# BiasController.net
KiCad netlist of a schematic drawn in EAGLE
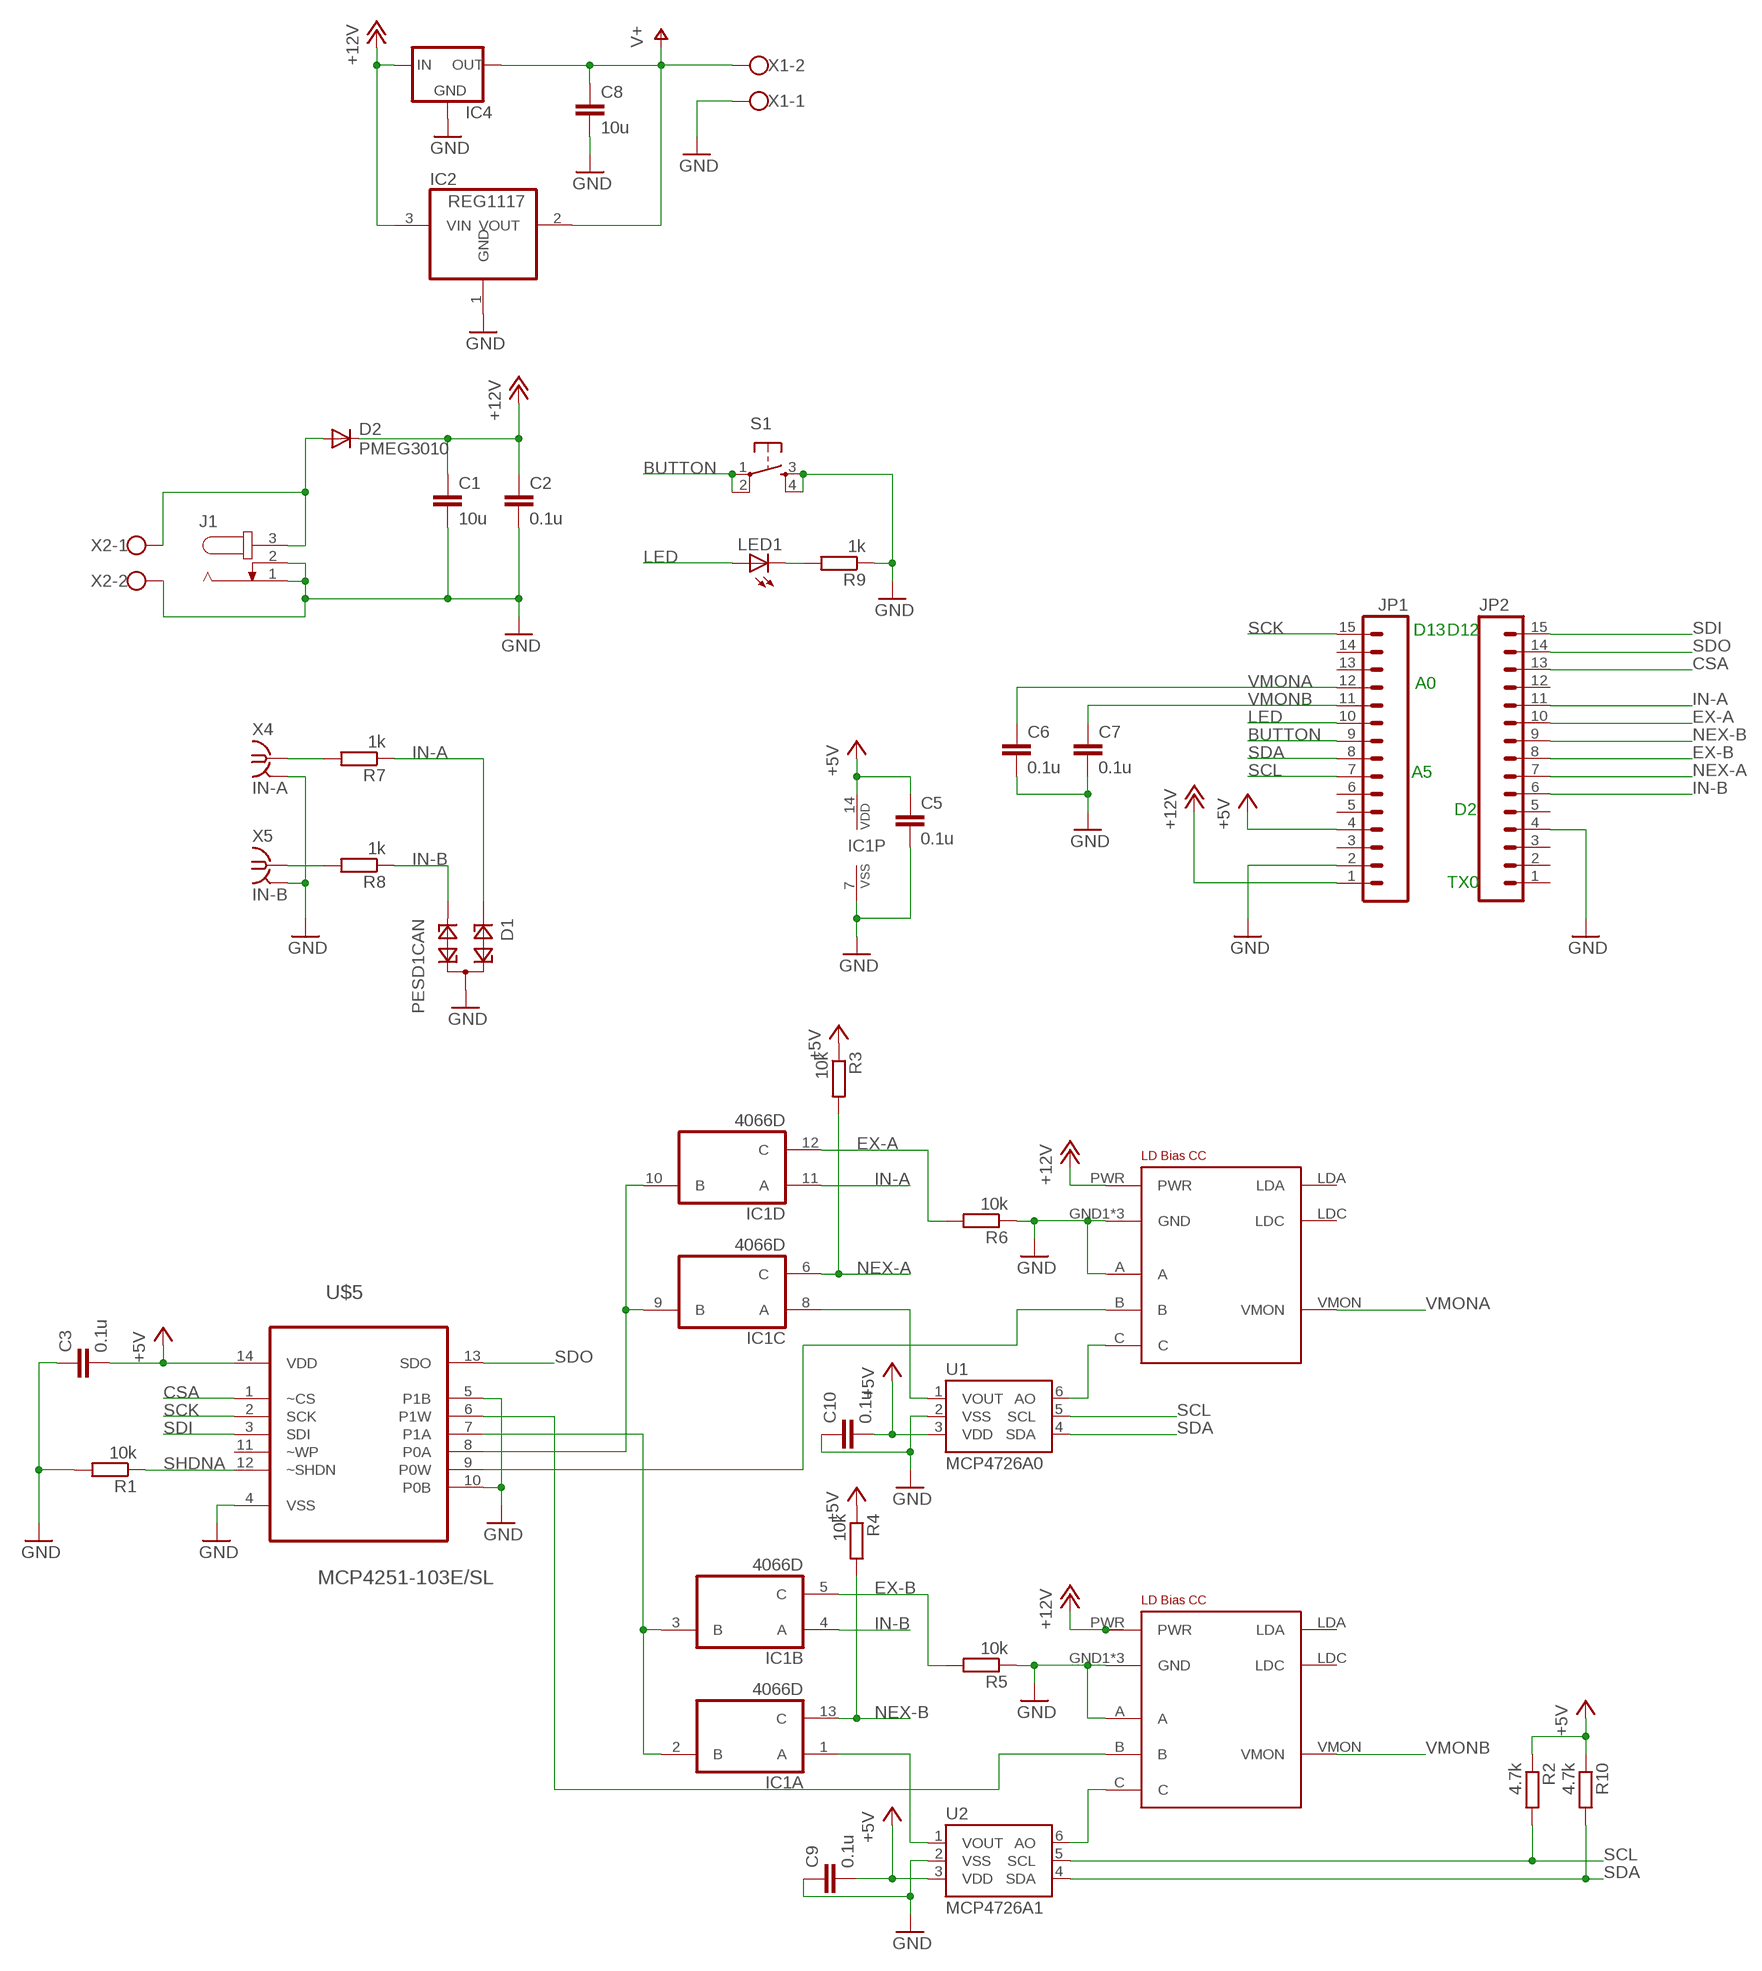
[diagram p0: schematic, sheet 1]

(export (version "E")
  (design (tool "Eeschema 10.0.6"))
  (components
    (comp (ref "C1")
      (value "10u")
      (footprint "eagle-import:C0805")
      (libsource (lib "eagle-import") (part "C-EUC0805"))
    )
    (comp (ref "C2")
      (value "0.1u")
      (footprint "eagle-import:C0805")
      (libsource (lib "eagle-import") (part "C-EUC0805"))
    )
    (comp (ref "C3")
      (value "0.1u")
      (footprint "eagle-import:C0805")
      (libsource (lib "eagle-import") (part "C-EUC0805"))
    )
    (comp (ref "C5")
      (value "0.1u")
      (footprint "eagle-import:C0805")
      (libsource (lib "eagle-import") (part "C-EUC0805"))
    )
    (comp (ref "C6")
      (value "0.1u")
      (footprint "eagle-import:C0805")
      (libsource (lib "eagle-import") (part "C-EUC0805"))
    )
    (comp (ref "C7")
      (value "0.1u")
      (footprint "eagle-import:C0805")
      (libsource (lib "eagle-import") (part "C-EUC0805"))
    )
    (comp (ref "C8")
      (value "10u")
      (footprint "eagle-import:C0805")
      (libsource (lib "eagle-import") (part "C-EUC0805"))
    )
    (comp (ref "C9")
      (value "0.1u")
      (footprint "eagle-import:C0805")
      (libsource (lib "eagle-import") (part "C-EUC0805"))
    )
    (comp (ref "C10")
      (value "0.1u")
      (footprint "eagle-import:C0805")
      (libsource (lib "eagle-import") (part "C-EUC0805"))
    )
    (comp (ref "D1")
      (value "PESD1CAN")
      (footprint "eagle-import:SOT23")
      (libsource (lib "eagle-import") (part "PESD1CAN"))
    )
    (comp (ref "D2")
      (value "PMEG3010")
      (footprint "eagle-import:SOD-323")
      (libsource (lib "eagle-import") (part "DIODESOD"))
    )
    (comp (ref "IC1")
      (value "4066D")
      (footprint "eagle-import:SO14")
      (libsource (lib "eagle-import") (part "4066D"))
    )
    (comp (ref "IC2")
      (value "REG1117")
      (footprint "eagle-import:SOT223")
      (libsource (lib "eagle-import") (part "REG1117"))
    )
    (comp (ref "IC4")
      (value "78XXS")
      (footprint "eagle-import:78XXS")
      (libsource (lib "eagle-import") (part "78XXS"))
    )
    (comp (ref "J1")
      (value "JACK-PLUG0")
      (footprint "eagle-import:SPC4077")
      (libsource (lib "eagle-import") (part "JACK-PLUG0"))
    )
    (comp (ref "JP1")
      (value "M15LOCK_LONGPADS")
      (footprint "eagle-import:1X15_LOCK_LONGPADS")
      (libsource (lib "eagle-import") (part "M15LOCK_LONGPADS"))
    )
    (comp (ref "JP2")
      (value "M15LOCK_LONGPADS")
      (footprint "eagle-import:1X15_LOCK_LONGPADS")
      (libsource (lib "eagle-import") (part "M15LOCK_LONGPADS"))
    )
    (comp (ref "LED1")
      (value "LED0603")
      (footprint "eagle-import:LED-0603")
      (libsource (lib "eagle-import") (part "LED0603"))
    )
    (comp (ref "R1")
      (value "10k")
      (footprint "eagle-import:R0805")
      (libsource (lib "eagle-import") (part "R-EU_R0805"))
    )
    (comp (ref "R2")
      (value "4.7k")
      (footprint "eagle-import:R0805")
      (libsource (lib "eagle-import") (part "R-EU_R0805"))
    )
    (comp (ref "R3")
      (value "10k")
      (footprint "eagle-import:R0805")
      (libsource (lib "eagle-import") (part "R-EU_R0805"))
    )
    (comp (ref "R4")
      (value "10k")
      (footprint "eagle-import:R0805")
      (libsource (lib "eagle-import") (part "R-EU_R0805"))
    )
    (comp (ref "R5")
      (value "10k")
      (footprint "eagle-import:R0805")
      (libsource (lib "eagle-import") (part "R-EU_R0805"))
    )
    (comp (ref "R6")
      (value "10k")
      (footprint "eagle-import:R0805")
      (libsource (lib "eagle-import") (part "R-EU_R0805"))
    )
    (comp (ref "R7")
      (value "1k")
      (footprint "eagle-import:R0805")
      (libsource (lib "eagle-import") (part "R-EU_R0805"))
    )
    (comp (ref "R8")
      (value "1k")
      (footprint "eagle-import:R0805")
      (libsource (lib "eagle-import") (part "R-EU_R0805"))
    )
    (comp (ref "R9")
      (value "1k")
      (footprint "eagle-import:R0805")
      (libsource (lib "eagle-import") (part "R-EU_R0805"))
    )
    (comp (ref "R10")
      (value "4.7k")
      (footprint "eagle-import:R0805")
      (libsource (lib "eagle-import") (part "R-EU_R0805"))
    )
    (comp (ref "S1")
      (value "TAC_SWITCHPTH")
      (footprint "eagle-import:TACTILE-PTH")
      (libsource (lib "eagle-import") (part "TAC_SWITCHPTH"))
    )
    (comp (ref "U$1")
      (value "LDBIASCC")
      (footprint "eagle-import:LDBIASDRIVERCC")
      (libsource (lib "eagle-import") (part "LDBIASCC"))
    )
    (comp (ref "U$2")
      (value "LDBIASCC")
      (footprint "eagle-import:LDBIASDRIVERCC")
      (libsource (lib "eagle-import") (part "LDBIASCC"))
    )
    (comp (ref "U$5")
      (value "MCP4251-103E/SL")
      (footprint "eagle-import:SOIC127P600X175-14N")
      (libsource (lib "eagle-import") (part "MCP4251-103E/SL"))
    )
    (comp (ref "U1")
      (value "MCP4726A0")
      (footprint "eagle-import:SOT23-6")
      (libsource (lib "eagle-import") (part "MCP4725SOT-23"))
    )
    (comp (ref "U2")
      (value "MCP4726A1")
      (footprint "eagle-import:SOT23-6")
      (libsource (lib "eagle-import") (part "MCP4725SOT-23"))
    )
    (comp (ref "X1")
      (value "W237-102")
      (footprint "eagle-import:W237-102")
      (fields (field (name "MPN") "237-102"))
      (libsource (lib "eagle-import") (part "W237-102"))
    )
    (comp (ref "X2")
      (value "W237-102")
      (footprint "eagle-import:W237-102")
      (fields (field (name "MPN") "237-102"))
      (libsource (lib "eagle-import") (part "W237-102"))
    )
    (comp (ref "X4")
      (value "IN-A")
      (footprint "eagle-import:J502-ND-142-0711-821_826")
      (fields (field (name "MF") "JOHNSON COMPONENTS") (field (name "MPN") "142-0711-821"))
      (libsource (lib "eagle-import") (part "SMA-142-0711-821/826"))
    )
    (comp (ref "X5")
      (value "IN-B")
      (footprint "eagle-import:J502-ND-142-0711-821_826")
      (fields (field (name "MF") "JOHNSON COMPONENTS") (field (name "MPN") "142-0711-821"))
      (libsource (lib "eagle-import") (part "SMA-142-0711-821/826"))
    )
  )
  (nets
    (net (code "1") (name "+5V") (class "Default")
      (node (ref "C10") (pin "2") (pinfunction "2_2") (pintype "passive"))
      (node (ref "C3") (pin "2") (pinfunction "2_2") (pintype "passive"))
      (node (ref "C5") (pin "1") (pinfunction "1_1") (pintype "passive"))
      (node (ref "C9") (pin "2") (pinfunction "2_2") (pintype "passive"))
      (node (ref "IC1") (pin "14") (pinfunction "VDD_14") (pintype "power_in"))
      (node (ref "JP1") (pin "4") (pinfunction "4_4") (pintype "passive"))
      (node (ref "R10") (pin "1") (pinfunction "1_1") (pintype "passive"))
      (node (ref "R2") (pin "1") (pinfunction "1_1") (pintype "passive"))
      (node (ref "R3") (pin "1") (pinfunction "1_1") (pintype "passive"))
      (node (ref "R4") (pin "1") (pinfunction "1_1") (pintype "passive"))
      (node (ref "U$5") (pin "14") (pinfunction "VDD_14") (pintype "power_in"))
      (node (ref "U1") (pin "3") (pinfunction "VDD_3") (pintype "bidirectional"))
      (node (ref "U2") (pin "3") (pinfunction "VDD_3") (pintype "bidirectional"))
    )
    (net (code "2") (name "+12V") (class "Default")
      (node (ref "C1") (pin "1") (pinfunction "1_1") (pintype "passive"))
      (node (ref "C2") (pin "1") (pinfunction "1_1") (pintype "passive"))
      (node (ref "D2") (pin "1") (pinfunction "C_1") (pintype "passive"))
      (node (ref "IC2") (pin "3") (pinfunction "VIN_3") (pintype "input"))
      (node (ref "IC4") (pin "IN") (pinfunction "IN_IN") (pintype "input"))
      (node (ref "JP1") (pin "1") (pinfunction "1_1") (pintype "passive"))
      (node (ref "U$1") (pin "PWR") (pinfunction "PWR_PWR") (pintype "bidirectional"))
      (node (ref "U$2") (pin "PWR") (pinfunction "PWR_PWR") (pintype "bidirectional"))
    )
    (net (code "3") (name "/BUTTON") (class "Default")
      (node (ref "JP1") (pin "9") (pinfunction "9_9") (pintype "passive"))
      (node (ref "S1") (pin "1") (pinfunction "1_1") (pintype "passive"))
      (node (ref "S1") (pin "2") (pinfunction "2_2") (pintype "passive"))
    )
    (net (code "4") (name "/CSA") (class "Default")
      (node (ref "JP2") (pin "13") (pinfunction "13_13") (pintype "passive"))
      (node (ref "U$5") (pin "1") (pinfunction "~{CS}_1") (pintype "input"))
    )
    (net (code "5") (name "/EX-A") (class "Default")
      (node (ref "IC1") (pin "12") (pinfunction "C_12") (pintype "input"))
      (node (ref "JP2") (pin "10") (pinfunction "10_10") (pintype "passive"))
      (node (ref "R6") (pin "2") (pinfunction "2_2") (pintype "passive"))
    )
    (net (code "6") (name "/EX-B") (class "Default")
      (node (ref "IC1") (pin "5") (pinfunction "C_5") (pintype "input"))
      (node (ref "JP2") (pin "8") (pinfunction "8_8") (pintype "passive"))
      (node (ref "R5") (pin "2") (pinfunction "2_2") (pintype "passive"))
    )
    (net (code "7") (name "/IN-A") (class "Default")
      (node (ref "D1") (pin "1") (pinfunction "1_1") (pintype "passive"))
      (node (ref "IC1") (pin "11") (pinfunction "A_11") (pintype "tri_state"))
      (node (ref "JP2") (pin "11") (pinfunction "11_11") (pintype "passive"))
      (node (ref "R7") (pin "1") (pinfunction "1_1") (pintype "passive"))
    )
    (net (code "8") (name "/IN-B") (class "Default")
      (node (ref "D1") (pin "2") (pinfunction "2_2") (pintype "passive"))
      (node (ref "IC1") (pin "4") (pinfunction "A_4") (pintype "tri_state"))
      (node (ref "JP2") (pin "6") (pinfunction "6_6") (pintype "passive"))
      (node (ref "R8") (pin "1") (pinfunction "1_1") (pintype "passive"))
    )
    (net (code "9") (name "/LED") (class "Default")
      (node (ref "JP1") (pin "10") (pinfunction "10_10") (pintype "passive"))
      (node (ref "LED1") (pin "A") (pinfunction "A_A") (pintype "passive"))
    )
    (net (code "10") (name "/NEX-A") (class "Default")
      (node (ref "IC1") (pin "6") (pinfunction "C_6") (pintype "input"))
      (node (ref "JP2") (pin "7") (pinfunction "7_7") (pintype "passive"))
      (node (ref "R3") (pin "2") (pinfunction "2_2") (pintype "passive"))
    )
    (net (code "11") (name "/NEX-B") (class "Default")
      (node (ref "IC1") (pin "13") (pinfunction "C_13") (pintype "input"))
      (node (ref "JP2") (pin "9") (pinfunction "9_9") (pintype "passive"))
      (node (ref "R4") (pin "2") (pinfunction "2_2") (pintype "passive"))
    )
    (net (code "12") (name "/SCK") (class "Default")
      (node (ref "JP1") (pin "15") (pinfunction "15_15") (pintype "passive"))
      (node (ref "U$5") (pin "2") (pinfunction "SCK_2") (pintype "input"))
    )
    (net (code "13") (name "/SCL") (class "Default")
      (node (ref "JP1") (pin "7") (pinfunction "7_7") (pintype "passive"))
      (node (ref "R2") (pin "2") (pinfunction "2_2") (pintype "passive"))
      (node (ref "U1") (pin "5") (pinfunction "SCL_5") (pintype "bidirectional"))
      (node (ref "U2") (pin "5") (pinfunction "SCL_5") (pintype "bidirectional"))
    )
    (net (code "14") (name "/SDA") (class "Default")
      (node (ref "JP1") (pin "8") (pinfunction "8_8") (pintype "passive"))
      (node (ref "R10") (pin "2") (pinfunction "2_2") (pintype "passive"))
      (node (ref "U1") (pin "4") (pinfunction "SDA_4") (pintype "bidirectional"))
      (node (ref "U2") (pin "4") (pinfunction "SDA_4") (pintype "bidirectional"))
    )
    (net (code "15") (name "/SDI") (class "Default")
      (node (ref "JP2") (pin "15") (pinfunction "15_15") (pintype "passive"))
      (node (ref "U$5") (pin "3") (pinfunction "SDI_3") (pintype "input"))
    )
    (net (code "16") (name "/SDO") (class "Default")
      (node (ref "JP2") (pin "14") (pinfunction "14_14") (pintype "passive"))
      (node (ref "U$5") (pin "13") (pinfunction "SDO_13") (pintype "output"))
    )
    (net (code "17") (name "/SHDNA") (class "Default")
      (node (ref "R1") (pin "1") (pinfunction "1_1") (pintype "passive"))
      (node (ref "U$5") (pin "12") (pinfunction "~{SHDN}_12") (pintype "input"))
    )
    (net (code "18") (name "/VMONA") (class "Default")
      (node (ref "C6") (pin "1") (pinfunction "1_1") (pintype "passive"))
      (node (ref "JP1") (pin "12") (pinfunction "12_12") (pintype "passive"))
      (node (ref "U$1") (pin "VMON") (pinfunction "VMON_VMON") (pintype "bidirectional"))
    )
    (net (code "19") (name "/VMONB") (class "Default")
      (node (ref "C7") (pin "1") (pinfunction "1_1") (pintype "passive"))
      (node (ref "JP1") (pin "11") (pinfunction "11_11") (pintype "passive"))
      (node (ref "U$2") (pin "VMON") (pinfunction "VMON_VMON") (pintype "bidirectional"))
    )
    (net (code "20") (name "GND") (class "Default")
      (node (ref "C1") (pin "2") (pinfunction "2_2") (pintype "passive"))
      (node (ref "C10") (pin "1") (pinfunction "1_1") (pintype "passive"))
      (node (ref "C2") (pin "2") (pinfunction "2_2") (pintype "passive"))
      (node (ref "C3") (pin "1") (pinfunction "1_1") (pintype "passive"))
      (node (ref "C5") (pin "2") (pinfunction "2_2") (pintype "passive"))
      (node (ref "C6") (pin "2") (pinfunction "2_2") (pintype "passive"))
      (node (ref "C7") (pin "2") (pinfunction "2_2") (pintype "passive"))
      (node (ref "C8") (pin "2") (pinfunction "2_2") (pintype "passive"))
      (node (ref "C9") (pin "1") (pinfunction "1_1") (pintype "passive"))
      (node (ref "D1") (pin "3") (pinfunction "3_3") (pintype "passive"))
      (node (ref "IC1") (pin "7") (pinfunction "VSS_7") (pintype "power_in"))
      (node (ref "IC2") (pin "1") (pinfunction "GND_1") (pintype "power_in"))
      (node (ref "IC4") (pin "GND") (pinfunction "GND_GND") (pintype "input"))
      (node (ref "J1") (pin "1") (pinfunction "1_1") (pintype "passive"))
      (node (ref "J1") (pin "2") (pinfunction "2_2") (pintype "passive"))
      (node (ref "JP1") (pin "2") (pinfunction "2_2") (pintype "passive"))
      (node (ref "JP2") (pin "4") (pinfunction "4_4") (pintype "passive"))
      (node (ref "R1") (pin "2") (pinfunction "2_2") (pintype "passive"))
      (node (ref "R5") (pin "1") (pinfunction "1_1") (pintype "passive"))
      (node (ref "R6") (pin "1") (pinfunction "1_1") (pintype "passive"))
      (node (ref "R9") (pin "1") (pinfunction "1_1") (pintype "passive"))
      (node (ref "S1") (pin "3") (pinfunction "3_3") (pintype "passive"))
      (node (ref "S1") (pin "4") (pinfunction "4_4") (pintype "passive"))
      (node (ref "U$1") (pin "A") (pinfunction "A_A") (pintype "bidirectional"))
      (node (ref "U$1") (pin "GND1") (pinfunction "GND_GND1") (pintype "bidirectional"))
      (node (ref "U$1") (pin "GND2") (pinfunction "GND_GND2") (pintype "bidirectional"))
      (node (ref "U$1") (pin "GND3") (pinfunction "GND_GND3") (pintype "bidirectional"))
      (node (ref "U$2") (pin "A") (pinfunction "A_A") (pintype "bidirectional"))
      (node (ref "U$2") (pin "GND1") (pinfunction "GND_GND1") (pintype "bidirectional"))
      (node (ref "U$2") (pin "GND2") (pinfunction "GND_GND2") (pintype "bidirectional"))
      (node (ref "U$2") (pin "GND3") (pinfunction "GND_GND3") (pintype "bidirectional"))
      (node (ref "U$5") (pin "10") (pinfunction "P0B_10") (pintype "bidirectional"))
      (node (ref "U$5") (pin "4") (pinfunction "VSS_4") (pintype "power_in"))
      (node (ref "U$5") (pin "5") (pinfunction "P1B_5") (pintype "bidirectional"))
      (node (ref "U1") (pin "2") (pinfunction "VSS_2") (pintype "bidirectional"))
      (node (ref "U2") (pin "2") (pinfunction "VSS_2") (pintype "bidirectional"))
      (node (ref "X1") (pin "1") (pinfunction "KL_1") (pintype "passive"))
      (node (ref "X2") (pin "2") (pinfunction "KL_2") (pintype "passive"))
      (node (ref "X4") (pin "G@1") (pinfunction "2_G@1") (pintype "passive"))
      (node (ref "X4") (pin "G@2") (pinfunction "2_G@2") (pintype "passive"))
      (node (ref "X4") (pin "G@3") (pinfunction "2_G@3") (pintype "passive"))
      (node (ref "X4") (pin "G@4") (pinfunction "2_G@4") (pintype "passive"))
      (node (ref "X5") (pin "G@1") (pinfunction "2_G@1") (pintype "passive"))
      (node (ref "X5") (pin "G@2") (pinfunction "2_G@2") (pintype "passive"))
      (node (ref "X5") (pin "G@3") (pinfunction "2_G@3") (pintype "passive"))
      (node (ref "X5") (pin "G@4") (pinfunction "2_G@4") (pintype "passive"))
    )
    (net (code "21") (name "Net-(D2-A)") (class "Default")
      (node (ref "D2") (pin "2") (pinfunction "A_2") (pintype "passive"))
      (node (ref "J1") (pin "3") (pinfunction "3_3") (pintype "passive"))
      (node (ref "X2") (pin "1") (pinfunction "KL_1") (pintype "passive"))
    )
    (net (code "22") (name "Net-(IC1A-A)") (class "Default")
      (node (ref "IC1") (pin "1") (pinfunction "A_1") (pintype "tri_state"))
      (node (ref "U2") (pin "1") (pinfunction "VOUT_1") (pintype "bidirectional"))
    )
    (net (code "23") (name "Net-(IC1A-B)") (class "Default")
      (node (ref "IC1") (pin "2") (pinfunction "B_2") (pintype "tri_state"))
      (node (ref "IC1") (pin "3") (pinfunction "B_3") (pintype "tri_state"))
      (node (ref "U$5") (pin "7") (pinfunction "P1A_7") (pintype "bidirectional"))
    )
    (net (code "24") (name "Net-(IC1C-A)") (class "Default")
      (node (ref "IC1") (pin "8") (pinfunction "A_8") (pintype "tri_state"))
      (node (ref "U1") (pin "1") (pinfunction "VOUT_1") (pintype "bidirectional"))
    )
    (net (code "25") (name "Net-(IC1C-B)") (class "Default")
      (node (ref "IC1") (pin "10") (pinfunction "B_10") (pintype "tri_state"))
      (node (ref "IC1") (pin "9") (pinfunction "B_9") (pintype "tri_state"))
      (node (ref "U$5") (pin "8") (pinfunction "P0A_8") (pintype "bidirectional"))
    )
    (net (code "26") (name "Net-(LED1-PadC)") (class "Default")
      (node (ref "LED1") (pin "C") (pinfunction "C_C") (pintype "passive"))
      (node (ref "R9") (pin "2") (pinfunction "2_2") (pintype "passive"))
    )
    (net (code "27") (name "Net-(R7-Pad2)") (class "Default")
      (node (ref "R7") (pin "2") (pinfunction "2_2") (pintype "passive"))
      (node (ref "X4") (pin "1") (pinfunction "1_1") (pintype "passive"))
    )
    (net (code "28") (name "Net-(R8-Pad2)") (class "Default")
      (node (ref "R8") (pin "2") (pinfunction "2_2") (pintype "passive"))
      (node (ref "X5") (pin "1") (pinfunction "1_1") (pintype "passive"))
    )
    (net (code "29") (name "Net-(U$5-P0W)") (class "Default")
      (node (ref "U$1") (pin "B") (pinfunction "B_B") (pintype "bidirectional"))
      (node (ref "U$5") (pin "9") (pinfunction "P0W_9") (pintype "bidirectional"))
    )
    (net (code "30") (name "Net-(U$5-P1W)") (class "Default")
      (node (ref "U$2") (pin "B") (pinfunction "B_B") (pintype "bidirectional"))
      (node (ref "U$5") (pin "6") (pinfunction "P1W_6") (pintype "bidirectional"))
    )
    (net (code "31") (name "Net-(U1-AO)") (class "Default")
      (node (ref "U$1") (pin "C") (pinfunction "C_C") (pintype "bidirectional"))
      (node (ref "U1") (pin "6") (pinfunction "AO_6") (pintype "bidirectional"))
    )
    (net (code "32") (name "Net-(U2-AO)") (class "Default")
      (node (ref "U$2") (pin "C") (pinfunction "C_C") (pintype "bidirectional"))
      (node (ref "U2") (pin "6") (pinfunction "AO_6") (pintype "bidirectional"))
    )
    (net (code "33") (name "V+") (class "Default")
      (node (ref "C8") (pin "1") (pinfunction "1_1") (pintype "passive"))
      (node (ref "IC2") (pin "2") (pinfunction "VOUT_2") (pintype "output"))
      (node (ref "IC4") (pin "OUT") (pinfunction "OUT_OUT") (pintype "passive"))
      (node (ref "X1") (pin "2") (pinfunction "KL_2") (pintype "passive"))
    )
    (net (code "34") (name "unconnected-(JP1-Pad3)") (class "Default")
      (node (ref "JP1") (pin "3") (pinfunction "3_3") (pintype "passive"))
    )
    (net (code "35") (name "unconnected-(JP1-Pad5)") (class "Default")
      (node (ref "JP1") (pin "5") (pinfunction "5_5") (pintype "passive"))
    )
    (net (code "36") (name "unconnected-(JP1-Pad6)") (class "Default")
      (node (ref "JP1") (pin "6") (pinfunction "6_6") (pintype "passive"))
    )
    (net (code "37") (name "unconnected-(JP1-Pad13)") (class "Default")
      (node (ref "JP1") (pin "13") (pinfunction "13_13") (pintype "passive"))
    )
    (net (code "38") (name "unconnected-(JP1-Pad14)") (class "Default")
      (node (ref "JP1") (pin "14") (pinfunction "14_14") (pintype "passive"))
    )
    (net (code "39") (name "unconnected-(JP2-Pad1)") (class "Default")
      (node (ref "JP2") (pin "1") (pinfunction "1_1") (pintype "passive"))
    )
    (net (code "40") (name "unconnected-(JP2-Pad2)") (class "Default")
      (node (ref "JP2") (pin "2") (pinfunction "2_2") (pintype "passive"))
    )
    (net (code "41") (name "unconnected-(JP2-Pad3)") (class "Default")
      (node (ref "JP2") (pin "3") (pinfunction "3_3") (pintype "passive"))
    )
    (net (code "42") (name "unconnected-(JP2-Pad5)") (class "Default")
      (node (ref "JP2") (pin "5") (pinfunction "5_5") (pintype "passive"))
    )
    (net (code "43") (name "unconnected-(JP2-Pad12)") (class "Default")
      (node (ref "JP2") (pin "12") (pinfunction "12_12") (pintype "passive"))
    )
    (net (code "44") (name "unconnected-(U$1-PadLDA)") (class "Default")
      (node (ref "U$1") (pin "LDA") (pinfunction "LDA_LDA") (pintype "bidirectional"))
    )
    (net (code "45") (name "unconnected-(U$1-PadLDC)") (class "Default")
      (node (ref "U$1") (pin "LDC") (pinfunction "LDC_LDC") (pintype "bidirectional"))
    )
    (net (code "46") (name "unconnected-(U$2-PadLDA)") (class "Default")
      (node (ref "U$2") (pin "LDA") (pinfunction "LDA_LDA") (pintype "bidirectional"))
    )
    (net (code "47") (name "unconnected-(U$2-PadLDC)") (class "Default")
      (node (ref "U$2") (pin "LDC") (pinfunction "LDC_LDC") (pintype "bidirectional"))
    )
    (net (code "48") (name "unconnected-(U$5-~{WP}-Pad11)") (class "Default")
      (node (ref "U$5") (pin "11") (pinfunction "~{WP}_11") (pintype "input"))
    )
  )
)
